# Distortion_Effect_Circuit.net
KiCad netlist of a schematic drawn in Altium Designer
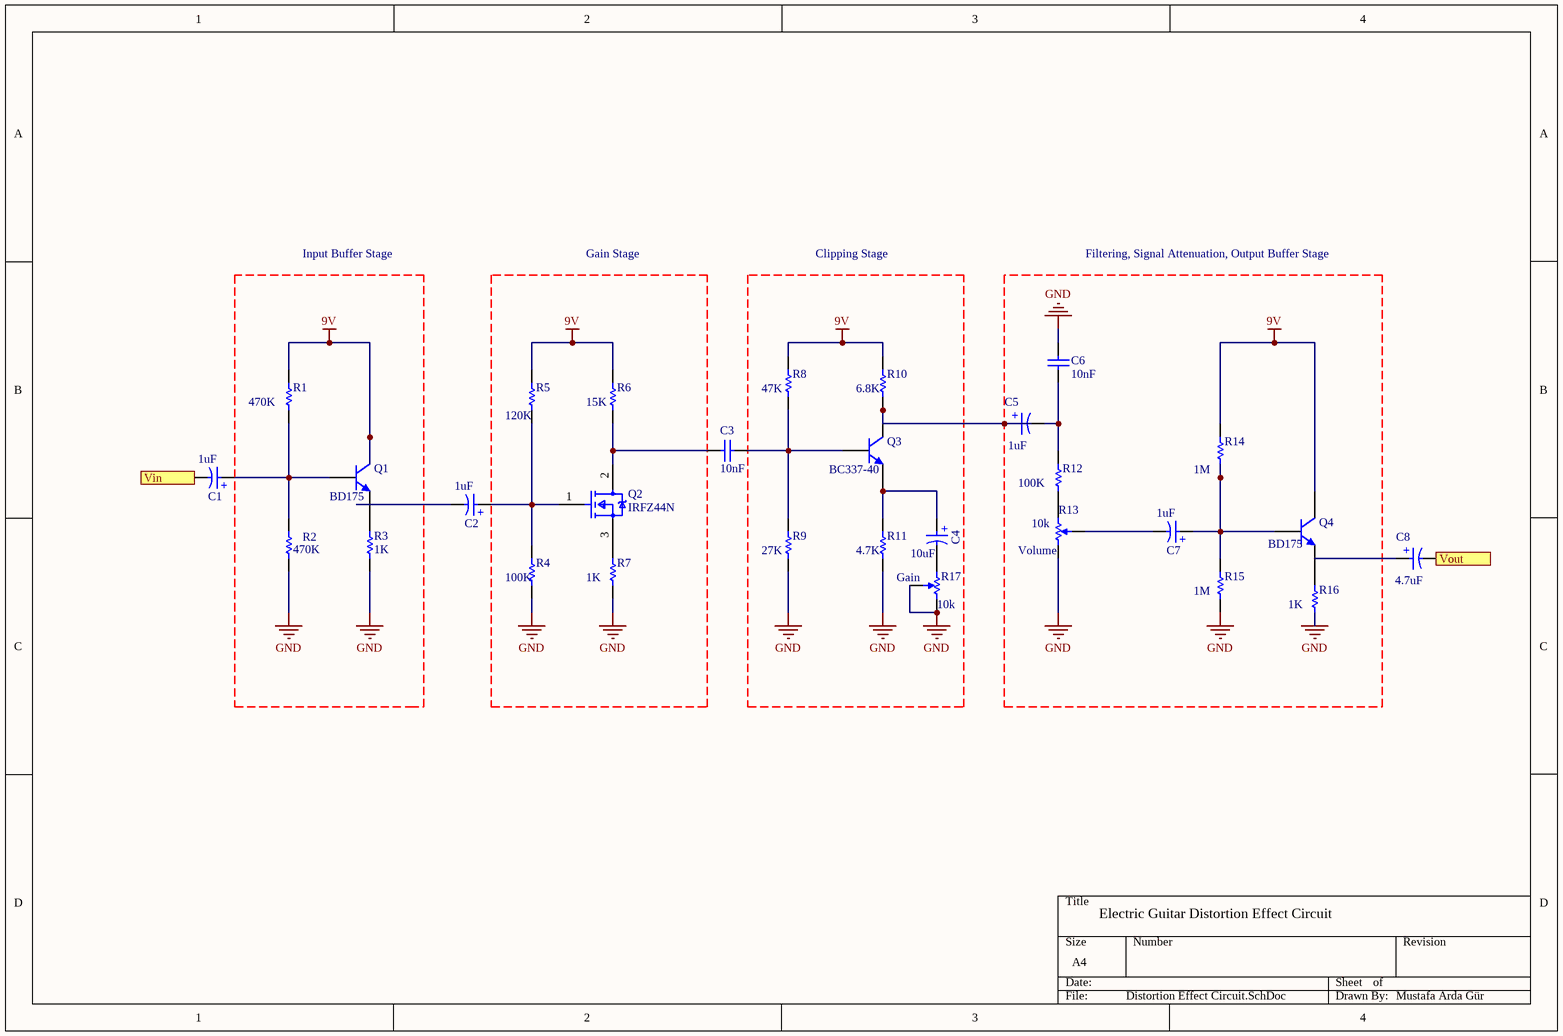
[diagram p0: Distortion Effect Circuit.SchDoc]

(export (version "E")
  (design (tool "Eeschema 10.0.6"))
  (components
    (comp (ref "C1")
      (value "1uF")
      (footprint "WCAP-ATG5_D5H11")
      (description "WCAP-ATG5 Aluminum Electrolytic Capacitors")
      (fields (field (name "TOLERANCE") "20%"))
      (libsource (lib "Altium Content Vault") (part "Capacitor_Polarized"))
    )
    (comp (ref "C2")
      (value "1uF")
      (footprint "WCAP-ATG5_D5H11")
      (description "WCAP-ATG5 Aluminum Electrolytic Capacitors")
      (fields (field (name "TOLERANCE") "20%"))
      (libsource (lib "Altium Content Vault") (part "Capacitor_Polarized"))
    )
    (comp (ref "C3")
      (value "10nF")
      (description "Capacitor")
      (libsource (lib "Simulation Generic Components") (part "Capacitor"))
    )
    (comp (ref "C4")
      (value "10uF")
      (footprint "WCAP-ATG5_D5H11")
      (description "WCAP-ATG5 Aluminum Electrolytic Capacitors")
      (fields (field (name "TOLERANCE") "20%"))
      (libsource (lib "Altium Content Vault") (part "Capacitor_Polarized"))
    )
    (comp (ref "C5")
      (value "1uF")
      (footprint "WCAP-ATG5_D5H11")
      (description "WCAP-ATG5 Aluminum Electrolytic Capacitors")
      (fields (field (name "TOLERANCE") "20%"))
      (libsource (lib "Altium Content Vault") (part "Capacitor_Polarized"))
    )
    (comp (ref "C6")
      (value "10nF")
      (description "Capacitor")
      (libsource (lib "Simulation Generic Components") (part "Capacitor"))
    )
    (comp (ref "C7")
      (value "1uF")
      (footprint "WCAP-ATG5_D5H11")
      (description "WCAP-ATG5 Aluminum Electrolytic Capacitors")
      (fields (field (name "TOLERANCE") "20%"))
      (libsource (lib "Altium Content Vault") (part "Capacitor_Polarized"))
    )
    (comp (ref "C8")
      (value "4.7uF")
      (footprint "WCAP-ATG5_D5H11")
      (description "WCAP-ATG5 Aluminum Electrolytic Capacitors")
      (fields (field (name "TOLERANCE") "20%"))
      (libsource (lib "Altium Content Vault") (part "Capacitor_Polarized"))
    )
    (comp (ref "Q1")
      (value "BD175")
      (description "Bipolar NPN 3 Pins Transistor VBIC Model")
      (libsource (lib "Simulation Generic Components") (part "BJT NPN VBIC"))
    )
    (comp (ref "Q2")
      (value "IRFZ44N")
      (footprint "FP-PG-TO262-3-MFG")
      (description "IRFZ44NLPBF Single N-Channel 55 V 17.5 mOhm 63 nC HEXFET® Power Mosfet - TO-262")
      (libsource (lib "Altium Content Vault") (part "b09f7f152735e370c1ea22a33fa83d6"))
    )
    (comp (ref "Q3")
      (value "BC337-40")
      (description "Bipolar NPN 3 Pins Transistor VBIC Model")
      (libsource (lib "Simulation Generic Components") (part "BJT NPN VBIC"))
    )
    (comp (ref "Q4")
      (value "BD175")
      (description "Bipolar NPN 3 Pins Transistor VBIC Model")
      (libsource (lib "Simulation Generic Components") (part "BJT NPN VBIC"))
    )
    (comp (ref "R1")
      (value "470K")
      (description "Resistor")
      (libsource (lib "Simulation Generic Components") (part "Resistor"))
    )
    (comp (ref "R2")
      (value "470K")
      (description "Resistor")
      (libsource (lib "Simulation Generic Components") (part "Resistor"))
    )
    (comp (ref "R3")
      (value "1K")
      (description "Resistor")
      (libsource (lib "Simulation Generic Components") (part "Resistor"))
    )
    (comp (ref "R4")
      (value "100K")
      (description "Resistor")
      (libsource (lib "Simulation Generic Components") (part "Resistor"))
    )
    (comp (ref "R5")
      (value "120K")
      (description "Resistor")
      (libsource (lib "Simulation Generic Components") (part "Resistor"))
    )
    (comp (ref "R6")
      (value "15K")
      (description "Resistor")
      (libsource (lib "Simulation Generic Components") (part "Resistor"))
    )
    (comp (ref "R7")
      (value "1K")
      (description "Resistor")
      (libsource (lib "Simulation Generic Components") (part "Resistor"))
    )
    (comp (ref "R8")
      (value "47K")
      (description "Resistor")
      (libsource (lib "Simulation Generic Components") (part "Resistor"))
    )
    (comp (ref "R9")
      (value "27K")
      (description "Resistor")
      (libsource (lib "Simulation Generic Components") (part "Resistor"))
    )
    (comp (ref "R10")
      (value "6.8K")
      (description "Resistor")
      (libsource (lib "Simulation Generic Components") (part "Resistor"))
    )
    (comp (ref "R11")
      (value "4.7K")
      (description "Resistor")
      (libsource (lib "Simulation Generic Components") (part "Resistor"))
    )
    (comp (ref "R12")
      (value "100K")
      (description "Resistor")
      (libsource (lib "Simulation Generic Components") (part "Resistor"))
    )
    (comp (ref "R13")
      (value "10k")
      (footprint "BI-35WR10KLFTR-3_V")
      (fields
        (field (name "MANUFACTURER") "BI Technologies")
        (field (name "POWER") "100mW")
        (field (name "TOLERANCE") "25%")
      )
      (libsource (lib "Mustafa Arda Gür") (part "RES-ADJ-3_A"))
    )
    (comp (ref "R14")
      (value "1M")
      (description "Resistor")
      (libsource (lib "Simulation Generic Components") (part "Resistor"))
    )
    (comp (ref "R15")
      (value "1M")
      (description "Resistor")
      (libsource (lib "Simulation Generic Components") (part "Resistor"))
    )
    (comp (ref "R16")
      (value "1K")
      (description "Resistor")
      (libsource (lib "Simulation Generic Components") (part "Resistor"))
    )
    (comp (ref "R17")
      (value "10k")
      (footprint "BI-35WR10KLFTR-3_V")
      (fields
        (field (name "MANUFACTURER") "BI Technologies")
        (field (name "POWER") "100mW")
        (field (name "TOLERANCE") "25%")
      )
      (libsource (lib "Mustafa Arda Gür") (part "RES-ADJ-3_A"))
    )
  )
  (nets
    (net (code "1") (name "/Vin") (class "Default")
      (node (ref "C1") (pin "2") (pinfunction "N_2") (pintype "passive"))
    )
    (net (code "2") (name "/Vout") (class "Default")
      (node (ref "C8") (pin "2") (pinfunction "N_2") (pintype "passive"))
    )
    (net (code "3") (name "9V") (class "Default")
      (node (ref "Q1") (pin "1") (pinfunction "C_1") (pintype "passive"))
      (node (ref "Q4") (pin "1") (pinfunction "C_1") (pintype "passive"))
      (node (ref "R1") (pin "2") (pinfunction "2_2") (pintype "passive"))
      (node (ref "R10") (pin "2") (pinfunction "2_2") (pintype "passive"))
      (node (ref "R14") (pin "2") (pinfunction "2_2") (pintype "passive"))
      (node (ref "R5") (pin "2") (pinfunction "2_2") (pintype "passive"))
      (node (ref "R6") (pin "2") (pinfunction "2_2") (pintype "passive"))
      (node (ref "R8") (pin "2") (pinfunction "2_2") (pintype "passive"))
    )
    (net (code "4") (name "GND") (class "Default")
      (node (ref "C6") (pin "2") (pinfunction "2_2") (pintype "passive"))
      (node (ref "R11") (pin "1") (pinfunction "1_1") (pintype "passive"))
      (node (ref "R13") (pin "1") (pinfunction "1_1") (pintype "passive"))
      (node (ref "R15") (pin "1") (pinfunction "1_1") (pintype "passive"))
      (node (ref "R16") (pin "1") (pinfunction "1_1") (pintype "passive"))
      (node (ref "R17") (pin "2") (pinfunction "2_2") (pintype "passive"))
      (node (ref "R17") (pin "3") (pinfunction "3_3") (pintype "passive"))
      (node (ref "R2") (pin "1") (pinfunction "1_1") (pintype "passive"))
      (node (ref "R3") (pin "1") (pinfunction "1_1") (pintype "passive"))
      (node (ref "R4") (pin "1") (pinfunction "1_1") (pintype "passive"))
      (node (ref "R7") (pin "1") (pinfunction "1_1") (pintype "passive"))
      (node (ref "R9") (pin "1") (pinfunction "1_1") (pintype "passive"))
    )
    (net (code "5") (name "Net-(C1-P)") (class "Default")
      (node (ref "C1") (pin "1") (pinfunction "P_1") (pintype "passive"))
      (node (ref "Q1") (pin "2") (pinfunction "B_2") (pintype "passive"))
      (node (ref "R1") (pin "1") (pinfunction "1_1") (pintype "passive"))
      (node (ref "R2") (pin "2") (pinfunction "2_2") (pintype "passive"))
    )
    (net (code "6") (name "Net-(C2-P)") (class "Default")
      (node (ref "C2") (pin "1") (pinfunction "P_1") (pintype "passive"))
      (node (ref "Q2") (pin "1") (pinfunction "G_1") (pintype "passive"))
      (node (ref "R4") (pin "2") (pinfunction "2_2") (pintype "passive"))
      (node (ref "R5") (pin "1") (pinfunction "1_1") (pintype "passive"))
    )
    (net (code "7") (name "Net-(C4-N)") (class "Default")
      (node (ref "C4") (pin "2") (pinfunction "N_2") (pintype "passive"))
      (node (ref "R17") (pin "1") (pinfunction "1_1") (pintype "passive"))
    )
    (net (code "8") (name "Net-(C4-P)") (class "Default")
      (node (ref "C4") (pin "1") (pinfunction "P_1") (pintype "passive"))
      (node (ref "Q3") (pin "3") (pinfunction "E_3") (pintype "passive"))
      (node (ref "R11") (pin "2") (pinfunction "2_2") (pintype "passive"))
    )
    (net (code "9") (name "Net-(C5-N)") (class "Default")
      (node (ref "C5") (pin "2") (pinfunction "N_2") (pintype "passive"))
      (node (ref "C6") (pin "1") (pinfunction "1_1") (pintype "passive"))
      (node (ref "R12") (pin "2") (pinfunction "2_2") (pintype "passive"))
    )
    (net (code "10") (name "Net-(C5-P)") (class "Default")
      (node (ref "C5") (pin "1") (pinfunction "P_1") (pintype "passive"))
      (node (ref "Q3") (pin "1") (pinfunction "C_1") (pintype "passive"))
      (node (ref "R10") (pin "1") (pinfunction "1_1") (pintype "passive"))
    )
    (net (code "11") (name "Net-(C7-N)") (class "Default")
      (node (ref "C7") (pin "2") (pinfunction "N_2") (pintype "passive"))
      (node (ref "R13") (pin "2") (pinfunction "2_2") (pintype "passive"))
    )
    (net (code "12") (name "Net-(C7-P)") (class "Default")
      (node (ref "C7") (pin "1") (pinfunction "P_1") (pintype "passive"))
      (node (ref "Q4") (pin "2") (pinfunction "B_2") (pintype "passive"))
      (node (ref "R14") (pin "1") (pinfunction "1_1") (pintype "passive"))
      (node (ref "R15") (pin "2") (pinfunction "2_2") (pintype "passive"))
    )
    (net (code "13") (name "Net-(Q1-E)") (class "Default")
      (node (ref "Q1") (pin "3") (pinfunction "E_3") (pintype "passive"))
      (node (ref "R3") (pin "2") (pinfunction "2_2") (pintype "passive"))
    )
    (net (code "14") (name "Net-(Q2-D)") (class "Default")
      (node (ref "C3") (pin "2") (pinfunction "2_2") (pintype "passive"))
      (node (ref "Q2") (pin "2") (pinfunction "D_2") (pintype "passive"))
      (node (ref "R6") (pin "1") (pinfunction "1_1") (pintype "passive"))
    )
    (net (code "15") (name "Net-(Q2-S)") (class "Default")
      (node (ref "Q2") (pin "3") (pinfunction "S_3") (pintype "passive"))
      (node (ref "R7") (pin "2") (pinfunction "2_2") (pintype "passive"))
    )
    (net (code "16") (name "Net-(Q3-B)") (class "Default")
      (node (ref "C3") (pin "1") (pinfunction "1_1") (pintype "passive"))
      (node (ref "Q3") (pin "2") (pinfunction "B_2") (pintype "passive"))
      (node (ref "R8") (pin "1") (pinfunction "1_1") (pintype "passive"))
      (node (ref "R9") (pin "2") (pinfunction "2_2") (pintype "passive"))
    )
    (net (code "17") (name "Net-(Q4-E)") (class "Default")
      (node (ref "Q4") (pin "3") (pinfunction "E_3") (pintype "passive"))
      (node (ref "R16") (pin "2") (pinfunction "2_2") (pintype "passive"))
    )
    (net (code "18") (name "Net-(R12-Pad1)") (class "Default")
      (node (ref "R12") (pin "1") (pinfunction "1_1") (pintype "passive"))
      (node (ref "R13") (pin "3") (pinfunction "3_3") (pintype "passive"))
    )
    (net (code "19") (name "unconnected-(C2-N-Pad2)") (class "Default")
      (node (ref "C2") (pin "2") (pinfunction "N_2") (pintype "passive"))
    )
    (net (code "20") (name "unconnected-(C8-P-Pad1)") (class "Default")
      (node (ref "C8") (pin "1") (pinfunction "P_1") (pintype "passive"))
    )
  )
)
